# MCU.net
KiCad netlist of a schematic drawn in Altium Designer
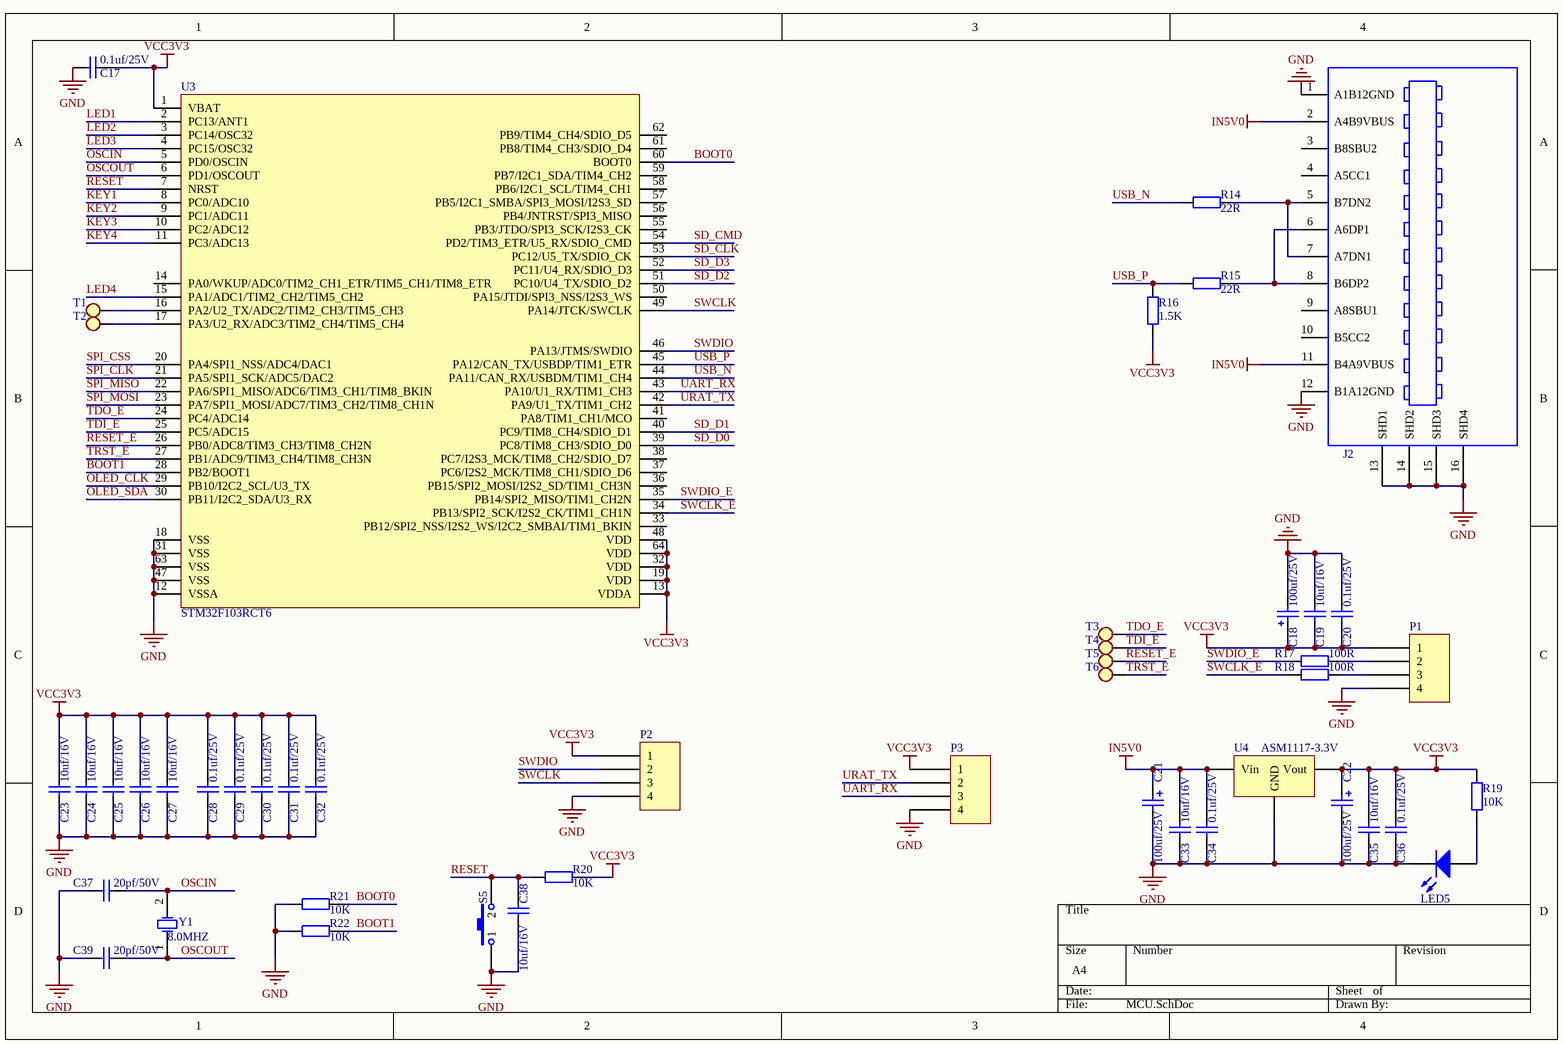
[diagram p0: MCU.SchDoc]

(export (version "E")
  (design (tool "Eeschema 10.0.6"))
  (components
    (comp (ref "C17")
      (value "0.1uf/25V")
      (footprint "R_C_L:C_0603")
      (description "多层片式陶瓷电容器")
      (libsource (lib "R_C_L") (part "C-0603-0.1uf/25V-10%"))
    )
    (comp (ref "C18")
      (value "100uf/25V")
      (footprint "R_C_L:C_6.3*5.4")
      (description "贴片电解电容")
      (libsource (lib "R_C_L") (part "C-6.3*5.8mm-100uf/25V-20%"))
    )
    (comp (ref "C19")
      (value "10uf/16V")
      (footprint "R_C_L:C_0603")
      (description "多层片式陶瓷电容器")
      (libsource (lib "R_C_L") (part "C-0603-10uf/16V-10%"))
    )
    (comp (ref "C20")
      (value "0.1uf/25V")
      (footprint "R_C_L:C_0603")
      (description "多层片式陶瓷电容器")
      (libsource (lib "R_C_L") (part "C-0603-0.1uf/25V-10%"))
    )
    (comp (ref "C21")
      (value "100uf/25V")
      (footprint "R_C_L:C_6.3*5.4")
      (description "贴片电解电容")
      (libsource (lib "R_C_L") (part "C-6.3*5.8mm-100uf/25V-20%"))
    )
    (comp (ref "C22")
      (value "100uf/25V")
      (footprint "R_C_L:C_6.3*5.4")
      (description "贴片电解电容")
      (libsource (lib "R_C_L") (part "C-6.3*5.8mm-100uf/25V-20%"))
    )
    (comp (ref "C23")
      (value "10uf/16V")
      (footprint "R_C_L:C_0603")
      (description "多层片式陶瓷电容器")
      (libsource (lib "R_C_L") (part "C-0603-10uf/16V-10%"))
    )
    (comp (ref "C24")
      (value "10uf/16V")
      (footprint "R_C_L:C_0603")
      (description "多层片式陶瓷电容器")
      (libsource (lib "R_C_L") (part "C-0603-10uf/16V-10%"))
    )
    (comp (ref "C25")
      (value "10uf/16V")
      (footprint "R_C_L:C_0603")
      (description "多层片式陶瓷电容器")
      (libsource (lib "R_C_L") (part "C-0603-10uf/16V-10%"))
    )
    (comp (ref "C26")
      (value "10uf/16V")
      (footprint "R_C_L:C_0603")
      (description "多层片式陶瓷电容器")
      (libsource (lib "R_C_L") (part "C-0603-10uf/16V-10%"))
    )
    (comp (ref "C27")
      (value "10uf/16V")
      (footprint "R_C_L:C_0603")
      (description "多层片式陶瓷电容器")
      (libsource (lib "R_C_L") (part "C-0603-10uf/16V-10%"))
    )
    (comp (ref "C28")
      (value "0.1uf/25V")
      (footprint "R_C_L:C_0603")
      (description "多层片式陶瓷电容器")
      (libsource (lib "R_C_L") (part "C-0603-0.1uf/25V-10%"))
    )
    (comp (ref "C29")
      (value "0.1uf/25V")
      (footprint "R_C_L:C_0603")
      (description "多层片式陶瓷电容器")
      (libsource (lib "R_C_L") (part "C-0603-0.1uf/25V-10%"))
    )
    (comp (ref "C30")
      (value "0.1uf/25V")
      (footprint "R_C_L:C_0603")
      (description "多层片式陶瓷电容器")
      (libsource (lib "R_C_L") (part "C-0603-0.1uf/25V-10%"))
    )
    (comp (ref "C31")
      (value "0.1uf/25V")
      (footprint "R_C_L:C_0603")
      (description "多层片式陶瓷电容器")
      (libsource (lib "R_C_L") (part "C-0603-0.1uf/25V-10%"))
    )
    (comp (ref "C32")
      (value "0.1uf/25V")
      (footprint "R_C_L:C_0603")
      (description "多层片式陶瓷电容器")
      (libsource (lib "R_C_L") (part "C-0603-0.1uf/25V-10%"))
    )
    (comp (ref "C33")
      (value "10uf/16V")
      (footprint "R_C_L:C_0603")
      (description "多层片式陶瓷电容器")
      (libsource (lib "R_C_L") (part "C-0603-10uf/16V-10%"))
    )
    (comp (ref "C34")
      (value "0.1uf/25V")
      (footprint "R_C_L:C_0603")
      (description "多层片式陶瓷电容器")
      (libsource (lib "R_C_L") (part "C-0603-0.1uf/25V-10%"))
    )
    (comp (ref "C35")
      (value "10uf/16V")
      (footprint "R_C_L:C_0603")
      (description "多层片式陶瓷电容器")
      (libsource (lib "R_C_L") (part "C-0603-10uf/16V-10%"))
    )
    (comp (ref "C36")
      (value "0.1uf/25V")
      (footprint "R_C_L:C_0603")
      (description "多层片式陶瓷电容器")
      (libsource (lib "R_C_L") (part "C-0603-0.1uf/25V-10%"))
    )
    (comp (ref "C37")
      (value "20pf/50V")
      (footprint "R_C_L:C_0603")
      (description "多层片式陶瓷电容器")
      (libsource (lib "R_C_L") (part "C-0603-20pf/50V-5%"))
    )
    (comp (ref "C38")
      (value "10uf/16V")
      (footprint "R_C_L:C_0603")
      (description "多层片式陶瓷电容器")
      (libsource (lib "R_C_L") (part "C-0603-10uf/16V-10%"))
    )
    (comp (ref "C39")
      (value "20pf/50V")
      (footprint "R_C_L:C_0603")
      (description "多层片式陶瓷电容器")
      (libsource (lib "R_C_L") (part "C-0603-20pf/50V-5%"))
    )
    (comp (ref "J2")
      (value "USB_TYPEC_YBT_2V0")
      (footprint "USB_TYPEC_YBD_USB31")
      (description "type-c母座16pin 快充闪充usb3.0沉板母座连接")
      (libsource (lib "HYG_Connector") (part "USB_TYPEC_YBT_2V0"))
    )
    (comp (ref "LED5")
      (value "19-21SYGC/S530-E2/TR8")
      (footprint "Transistor:LED_0603")
      (description "发光二极管0603黄绿色")
      (libsource (lib "Transistor") (part "LED1_19-21SYGC/S530-E2/TR8"))
    )
    (comp (ref "P1")
      (value "A2543WR-4P-2")
      (footprint "XH2.54-LI-4P")
      (libsource (lib "Connector") (part "Header 4*1   2.54mm直插  A2543WR-4P-2"))
    )
    (comp (ref "P2")
      (value "210S-1*4P L=11.6MM镀金")
      (footprint "Connector:CON2.54-4P-A-DIP")
      (libsource (lib "Connector") (part "Header 4*1   2.54mm直插  210S-1*4P L=11.6MM镀金"))
    )
    (comp (ref "P3")
      (value "210S-1*4P L=11.6MM镀金")
      (footprint "Connector:CON2.54-4P-A-DIP")
      (libsource (lib "Connector") (part "Header 4*1   2.54mm直插  210S-1*4P L=11.6MM镀金"))
    )
    (comp (ref "R14")
      (value "22R")
      (footprint "R_C_L:R_0603")
      (description "通用电阻")
      (libsource (lib "R_C_L") (part "R-0603-22R-1%"))
    )
    (comp (ref "R15")
      (value "22R")
      (footprint "R_C_L:R_0603")
      (description "通用电阻")
      (libsource (lib "R_C_L") (part "R-0603-22R-1%"))
    )
    (comp (ref "R16")
      (value "1.5K")
      (footprint "R_C_L:R_0603")
      (description "通用电阻")
      (libsource (lib "R_C_L") (part "R-0603-1.5K-1%"))
    )
    (comp (ref "R17")
      (value "100R")
      (footprint "R_C_L:R_0603")
      (description "通用电阻")
      (libsource (lib "R_C_L") (part "R-0603-100R-1%"))
    )
    (comp (ref "R18")
      (value "100R")
      (footprint "R_C_L:R_0603")
      (description "通用电阻")
      (libsource (lib "R_C_L") (part "R-0603-100R-1%"))
    )
    (comp (ref "R19")
      (value "10K")
      (footprint "R_C_L:R_0603")
      (description "通用电阻")
      (libsource (lib "R_C_L") (part "R-0603-10K-1%"))
    )
    (comp (ref "R20")
      (value "10K")
      (footprint "R_C_L:R_0603")
      (description "通用电阻")
      (libsource (lib "") (part "R-0603-10K-1%_1"))
    )
    (comp (ref "R21")
      (value "10K")
      (footprint "R_C_L:R_0603")
      (description "通用电阻")
      (libsource (lib "") (part "R-0603-10K-1%_1"))
    )
    (comp (ref "R22")
      (value "10K")
      (footprint "R_C_L:R_0603")
      (description "通用电阻")
      (libsource (lib "") (part "R-0603-10K-1%_1"))
    )
    (comp (ref "S5")
      (value "K2-1107ST-A4SW-06")
      (footprint "NSP:SW-2P-6*3-SMT")
      (description "轻触开关3.6*6.1*2.5")
      (libsource (lib "NSP") (part "KEY_K2-1107ST-A4SW-06"))
    )
    (comp (ref "T1")
      (value "TEST POINT_SMD")
      (footprint "NSP:TEST POINT-SMD")
      (description "测试点")
      (libsource (lib "NSP") (part "TEST POINT_SMD"))
    )
    (comp (ref "T2")
      (value "TEST POINT_SMD")
      (footprint "NSP:TEST POINT-SMD")
      (description "测试点")
      (libsource (lib "NSP") (part "TEST POINT_SMD"))
    )
    (comp (ref "T3")
      (value "TEST POINT_SMD")
      (footprint "NSP:TEST POINT-SMD")
      (description "测试点")
      (libsource (lib "NSP") (part "TEST POINT_SMD"))
    )
    (comp (ref "T4")
      (value "TEST POINT_SMD")
      (footprint "NSP:TEST POINT-SMD")
      (description "测试点")
      (libsource (lib "NSP") (part "TEST POINT_SMD"))
    )
    (comp (ref "T5")
      (value "TEST POINT_SMD")
      (footprint "NSP:TEST POINT-SMD")
      (description "测试点")
      (libsource (lib "NSP") (part "TEST POINT_SMD"))
    )
    (comp (ref "T6")
      (value "TEST POINT_SMD")
      (footprint "NSP:TEST POINT-SMD")
      (description "测试点")
      (libsource (lib "NSP") (part "TEST POINT_SMD"))
    )
    (comp (ref "U3")
      (value "STM32F103RCT6")
      (footprint "Digital:LQFP64")
      (description "Cortex-M3核心ARM控制器 72MHz主频 64pin引脚LQFP64")
      (libsource (lib "Digital") (part "STM32F103RCT6"))
    )
    (comp (ref "U4")
      (value "ASM1117-3.3V")
      (footprint "Power:SOT223")
      (description "三端稳压器")
      (libsource (lib "Power") (part "ASM1117-3.3V"))
    )
    (comp (ref "Y1")
      (value "8.0MHZ")
      (footprint "XTAL_5032")
      (description "晶体振荡器  5032-2P   8M")
      (libsource (lib "NSP") (part "XTAL_ABM3B-8.000MHZ-10-1-U-T"))
    )
  )
  (nets
    (net (code "1") (name "/BOOT0") (class "Default")
      (node (ref "R21") (pin "2") (pinfunction "2_2") (pintype "passive"))
      (node (ref "U3") (pin "60") (pinfunction "BOOT0_60") (pintype "passive"))
    )
    (net (code "2") (name "/BOOT1") (class "Default")
      (node (ref "R22") (pin "2") (pinfunction "2_2") (pintype "passive"))
      (node (ref "U3") (pin "28") (pinfunction "PB2/BOOT1_28") (pintype "passive"))
    )
    (net (code "3") (name "/KEY1") (class "Default")
      (node (ref "U3") (pin "8") (pinfunction "PC0/ADC10_8") (pintype "passive"))
    )
    (net (code "4") (name "/KEY2") (class "Default")
      (node (ref "U3") (pin "9") (pinfunction "PC1/ADC11_9") (pintype "passive"))
    )
    (net (code "5") (name "/KEY3") (class "Default")
      (node (ref "U3") (pin "10") (pinfunction "PC2/ADC12_10") (pintype "passive"))
    )
    (net (code "6") (name "/KEY4") (class "Default")
      (node (ref "U3") (pin "11") (pinfunction "PC3/ADC13_11") (pintype "passive"))
    )
    (net (code "7") (name "/LED1") (class "Default")
      (node (ref "U3") (pin "2") (pinfunction "PC13/ANT1_2") (pintype "passive"))
    )
    (net (code "8") (name "/LED2") (class "Default")
      (node (ref "U3") (pin "3") (pinfunction "PC14/OSC32_3") (pintype "passive"))
    )
    (net (code "9") (name "/LED3") (class "Default")
      (node (ref "U3") (pin "4") (pinfunction "PC15/OSC32_4") (pintype "passive"))
    )
    (net (code "10") (name "/LED4") (class "Default")
      (node (ref "U3") (pin "15") (pinfunction "PA1/ADC1/TIM2_CH2/TIM5_CH2_15") (pintype "passive"))
    )
    (net (code "11") (name "/OLED_CLK") (class "Default")
      (node (ref "U3") (pin "29") (pinfunction "PB10/I2C2_SCL/U3_TX_29") (pintype "passive"))
    )
    (net (code "12") (name "/OLED_SDA") (class "Default")
      (node (ref "U3") (pin "30") (pinfunction "PB11/I2C2_SDA/U3_RX_30") (pintype "passive"))
    )
    (net (code "13") (name "/OSCIN") (class "Default")
      (node (ref "C37") (pin "2") (pinfunction "2_2") (pintype "passive"))
      (node (ref "U3") (pin "5") (pinfunction "PD0/OSCIN_5") (pintype "passive"))
      (node (ref "Y1") (pin "2") (pinfunction "OSC2_2") (pintype "passive"))
    )
    (net (code "14") (name "/OSCOUT") (class "Default")
      (node (ref "C39") (pin "2") (pinfunction "2_2") (pintype "passive"))
      (node (ref "U3") (pin "6") (pinfunction "PD1/OSCOUT_6") (pintype "passive"))
      (node (ref "Y1") (pin "1") (pinfunction "OSC1_1") (pintype "passive"))
    )
    (net (code "15") (name "/RESET") (class "Default")
      (node (ref "C38") (pin "2") (pinfunction "2_2") (pintype "passive"))
      (node (ref "R20") (pin "1") (pinfunction "1_1") (pintype "passive"))
      (node (ref "S5") (pin "2") (pinfunction "2_2") (pintype "passive"))
      (node (ref "U3") (pin "7") (pinfunction "NRST_7") (pintype "passive"))
    )
    (net (code "16") (name "/RESET_E") (class "Default")
      (node (ref "T5") (pin "1") (pinfunction "1_1") (pintype "passive"))
      (node (ref "U3") (pin "26") (pinfunction "PB0/ADC8/TIM3_CH3/TIM8_CH2N_26") (pintype "passive"))
    )
    (net (code "17") (name "/SD_CLK") (class "Default")
      (node (ref "U3") (pin "53") (pinfunction "PC12/U5_TX/SDIO_CK_53") (pintype "passive"))
    )
    (net (code "18") (name "/SD_CMD") (class "Default")
      (node (ref "U3") (pin "54") (pinfunction "PD2/TIM3_ETR/U5_RX/SDIO_CMD_54") (pintype "passive"))
    )
    (net (code "19") (name "/SD_D0") (class "Default")
      (node (ref "U3") (pin "39") (pinfunction "PC8/TIM8_CH3/SDIO_D0_39") (pintype "passive"))
    )
    (net (code "20") (name "/SD_D1") (class "Default")
      (node (ref "U3") (pin "40") (pinfunction "PC9/TIM8_CH4/SDIO_D1_40") (pintype "passive"))
    )
    (net (code "21") (name "/SD_D2") (class "Default")
      (node (ref "U3") (pin "51") (pinfunction "PC10/U4_TX/SDIO_D2_51") (pintype "passive"))
    )
    (net (code "22") (name "/SD_D3") (class "Default")
      (node (ref "U3") (pin "52") (pinfunction "PC11/U4_RX/SDIO_D3_52") (pintype "passive"))
    )
    (net (code "23") (name "/SPI_CLK") (class "Default")
      (node (ref "U3") (pin "21") (pinfunction "PA5/SPI1_SCK/ADC5/DAC2_21") (pintype "passive"))
    )
    (net (code "24") (name "/SPI_CSS") (class "Default")
      (node (ref "U3") (pin "20") (pinfunction "PA4/SPI1_NSS/ADC4/DAC1_20") (pintype "passive"))
    )
    (net (code "25") (name "/SPI_MISO") (class "Default")
      (node (ref "U3") (pin "22") (pinfunction "PA6/SPI1_MISO/ADC6/TIM3_CH1/TIM8_BKIN_22") (pintype "passive"))
    )
    (net (code "26") (name "/SPI_MOSI") (class "Default")
      (node (ref "U3") (pin "23") (pinfunction "PA7/SPI1_MOSI/ADC7/TIM3_CH2/TIM8_CH1N_23") (pintype "passive"))
    )
    (net (code "27") (name "/SWCLK") (class "Default")
      (node (ref "P2") (pin "3") (pinfunction "3_3") (pintype "passive"))
      (node (ref "U3") (pin "49") (pinfunction "PA14/JTCK/SWCLK_49") (pintype "passive"))
    )
    (net (code "28") (name "/SWCLK_E") (class "Default")
      (node (ref "R18") (pin "1") (pinfunction "1_1") (pintype "passive"))
      (node (ref "U3") (pin "34") (pinfunction "PB13/SPI2_SCK/I2S2_CK/TIM1_CH1N_34") (pintype "passive"))
    )
    (net (code "29") (name "/SWDIO") (class "Default")
      (node (ref "P2") (pin "2") (pinfunction "2_2") (pintype "passive"))
      (node (ref "U3") (pin "46") (pinfunction "PA13/JTMS/SWDIO_46") (pintype "passive"))
    )
    (net (code "30") (name "/SWDIO_E") (class "Default")
      (node (ref "R17") (pin "1") (pinfunction "1_1") (pintype "passive"))
      (node (ref "U3") (pin "35") (pinfunction "PB14/SPI2_MISO/TIM1_CH2N_35") (pintype "passive"))
    )
    (net (code "31") (name "/TDI_E") (class "Default")
      (node (ref "T4") (pin "1") (pinfunction "1_1") (pintype "passive"))
      (node (ref "U3") (pin "25") (pinfunction "PC5/ADC15_25") (pintype "passive"))
    )
    (net (code "32") (name "/TDO_E") (class "Default")
      (node (ref "T3") (pin "1") (pinfunction "1_1") (pintype "passive"))
      (node (ref "U3") (pin "24") (pinfunction "PC4/ADC14_24") (pintype "passive"))
    )
    (net (code "33") (name "/TRST_E") (class "Default")
      (node (ref "T6") (pin "1") (pinfunction "1_1") (pintype "passive"))
      (node (ref "U3") (pin "27") (pinfunction "PB1/ADC9/TIM3_CH4/TIM8_CH3N_27") (pintype "passive"))
    )
    (net (code "34") (name "/UART_RX") (class "Default")
      (node (ref "P3") (pin "3") (pinfunction "3_3") (pintype "passive"))
      (node (ref "U3") (pin "43") (pinfunction "PA10/U1_RX/TIM1_CH3_43") (pintype "passive"))
    )
    (net (code "35") (name "/URAT_TX") (class "Default")
      (node (ref "P3") (pin "2") (pinfunction "2_2") (pintype "passive"))
      (node (ref "U3") (pin "42") (pinfunction "PA9/U1_TX/TIM1_CH2_42") (pintype "passive"))
    )
    (net (code "36") (name "/USB_N") (class "Default")
      (node (ref "R14") (pin "1") (pinfunction "1_1") (pintype "passive"))
      (node (ref "U3") (pin "44") (pinfunction "PA11/CAN_RX/USBDM/TIM1_CH4_44") (pintype "passive"))
    )
    (net (code "37") (name "/USB_P") (class "Default")
      (node (ref "R15") (pin "1") (pinfunction "1_1") (pintype "passive"))
      (node (ref "R16") (pin "2") (pinfunction "2_2") (pintype "passive"))
      (node (ref "U3") (pin "45") (pinfunction "PA12/CAN_TX/USBDP/TIM1_ETR_45") (pintype "passive"))
    )
    (net (code "38") (name "GND") (class "Default")
      (node (ref "C17") (pin "1") (pinfunction "1_1") (pintype "passive"))
      (node (ref "C18") (pin "2") (pinfunction "2_2") (pintype "passive"))
      (node (ref "C19") (pin "2") (pinfunction "2_2") (pintype "passive"))
      (node (ref "C20") (pin "2") (pinfunction "2_2") (pintype "passive"))
      (node (ref "C21") (pin "2") (pinfunction "2_2") (pintype "passive"))
      (node (ref "C22") (pin "2") (pinfunction "2_2") (pintype "passive"))
      (node (ref "C23") (pin "1") (pinfunction "1_1") (pintype "passive"))
      (node (ref "C24") (pin "1") (pinfunction "1_1") (pintype "passive"))
      (node (ref "C25") (pin "1") (pinfunction "1_1") (pintype "passive"))
      (node (ref "C26") (pin "1") (pinfunction "1_1") (pintype "passive"))
      (node (ref "C27") (pin "1") (pinfunction "1_1") (pintype "passive"))
      (node (ref "C28") (pin "1") (pinfunction "1_1") (pintype "passive"))
      (node (ref "C29") (pin "1") (pinfunction "1_1") (pintype "passive"))
      (node (ref "C30") (pin "1") (pinfunction "1_1") (pintype "passive"))
      (node (ref "C31") (pin "1") (pinfunction "1_1") (pintype "passive"))
      (node (ref "C32") (pin "1") (pinfunction "1_1") (pintype "passive"))
      (node (ref "C33") (pin "1") (pinfunction "1_1") (pintype "passive"))
      (node (ref "C34") (pin "1") (pinfunction "1_1") (pintype "passive"))
      (node (ref "C35") (pin "1") (pinfunction "1_1") (pintype "passive"))
      (node (ref "C36") (pin "1") (pinfunction "1_1") (pintype "passive"))
      (node (ref "C37") (pin "1") (pinfunction "1_1") (pintype "passive"))
      (node (ref "C38") (pin "1") (pinfunction "1_1") (pintype "passive"))
      (node (ref "C39") (pin "1") (pinfunction "1_1") (pintype "passive"))
      (node (ref "J2") (pin "1") (pinfunction "A1B12GND_1") (pintype "passive"))
      (node (ref "J2") (pin "12") (pinfunction "B1A12GND_12") (pintype "passive"))
      (node (ref "J2") (pin "13") (pinfunction "SHD1_13") (pintype "passive"))
      (node (ref "J2") (pin "14") (pinfunction "SHD2_14") (pintype "passive"))
      (node (ref "J2") (pin "15") (pinfunction "SHD3_15") (pintype "passive"))
      (node (ref "J2") (pin "16") (pinfunction "SHD4_16") (pintype "passive"))
      (node (ref "LED5") (pin "2") (pinfunction "Cathode_2") (pintype "passive"))
      (node (ref "P1") (pin "4") (pinfunction "4_4") (pintype "passive"))
      (node (ref "P2") (pin "4") (pinfunction "4_4") (pintype "passive"))
      (node (ref "P3") (pin "4") (pinfunction "4_4") (pintype "passive"))
      (node (ref "R21") (pin "1") (pinfunction "1_1") (pintype "passive"))
      (node (ref "R22") (pin "1") (pinfunction "1_1") (pintype "passive"))
      (node (ref "S5") (pin "1") (pinfunction "1_1") (pintype "passive"))
      (node (ref "U3") (pin "12") (pinfunction "VSSA_12") (pintype "passive"))
      (node (ref "U3") (pin "18") (pinfunction "VSS_18") (pintype "passive"))
      (node (ref "U3") (pin "31") (pinfunction "VSS_31") (pintype "passive"))
      (node (ref "U3") (pin "47") (pinfunction "VSS_47") (pintype "passive"))
      (node (ref "U3") (pin "63") (pinfunction "VSS_63") (pintype "passive"))
      (node (ref "U4") (pin "1") (pinfunction "GND_1") (pintype "passive"))
    )
    (net (code "39") (name "IN5V0") (class "Default")
      (node (ref "C21") (pin "1") (pinfunction "1_1") (pintype "passive"))
      (node (ref "C33") (pin "2") (pinfunction "2_2") (pintype "passive"))
      (node (ref "C34") (pin "2") (pinfunction "2_2") (pintype "passive"))
      (node (ref "J2") (pin "11") (pinfunction "B4A9VBUS_11") (pintype "passive"))
      (node (ref "J2") (pin "2") (pinfunction "A4B9VBUS_2") (pintype "passive"))
      (node (ref "U4") (pin "3") (pinfunction "Vin_3") (pintype "passive"))
    )
    (net (code "40") (name "Net-(J2-A6DP1)") (class "Default")
      (node (ref "J2") (pin "6") (pinfunction "A6DP1_6") (pintype "passive"))
      (node (ref "J2") (pin "8") (pinfunction "B6DP2_8") (pintype "passive"))
      (node (ref "R15") (pin "2") (pinfunction "2_2") (pintype "passive"))
    )
    (net (code "41") (name "Net-(J2-A7DN1)") (class "Default")
      (node (ref "J2") (pin "5") (pinfunction "B7DN2_5") (pintype "passive"))
      (node (ref "J2") (pin "7") (pinfunction "A7DN1_7") (pintype "passive"))
      (node (ref "R14") (pin "2") (pinfunction "2_2") (pintype "passive"))
    )
    (net (code "42") (name "Net-(LED5-Anode)") (class "Default")
      (node (ref "LED5") (pin "1") (pinfunction "Anode_1") (pintype "passive"))
      (node (ref "R19") (pin "1") (pinfunction "1_1") (pintype "passive"))
    )
    (net (code "43") (name "Net-(P1-Pad2)") (class "Default")
      (node (ref "P1") (pin "2") (pinfunction "2_2") (pintype "passive"))
      (node (ref "R17") (pin "2") (pinfunction "2_2") (pintype "passive"))
    )
    (net (code "44") (name "Net-(P1-Pad3)") (class "Default")
      (node (ref "P1") (pin "3") (pinfunction "3_3") (pintype "passive"))
      (node (ref "R18") (pin "2") (pinfunction "2_2") (pintype "passive"))
    )
    (net (code "45") (name "Net-(U3-PA2{slash}U2_TX{slash}ADC2{slash}TIM2_CH3{slash}TIM5_CH3)") (class "Default")
      (node (ref "T1") (pin "1") (pinfunction "1_1") (pintype "passive"))
      (node (ref "U3") (pin "16") (pinfunction "PA2/U2_TX/ADC2/TIM2_CH3/TIM5_CH3_16") (pintype "passive"))
    )
    (net (code "46") (name "Net-(U3-PA3{slash}U2_RX{slash}ADC3{slash}TIM2_CH4{slash}TIM5_CH4)") (class "Default")
      (node (ref "T2") (pin "1") (pinfunction "1_1") (pintype "passive"))
      (node (ref "U3") (pin "17") (pinfunction "PA3/U2_RX/ADC3/TIM2_CH4/TIM5_CH4_17") (pintype "passive"))
    )
    (net (code "47") (name "VCC3V3") (class "Default")
      (node (ref "C17") (pin "2") (pinfunction "2_2") (pintype "passive"))
      (node (ref "C18") (pin "1") (pinfunction "1_1") (pintype "passive"))
      (node (ref "C19") (pin "1") (pinfunction "1_1") (pintype "passive"))
      (node (ref "C20") (pin "1") (pinfunction "1_1") (pintype "passive"))
      (node (ref "C22") (pin "1") (pinfunction "1_1") (pintype "passive"))
      (node (ref "C23") (pin "2") (pinfunction "2_2") (pintype "passive"))
      (node (ref "C24") (pin "2") (pinfunction "2_2") (pintype "passive"))
      (node (ref "C25") (pin "2") (pinfunction "2_2") (pintype "passive"))
      (node (ref "C26") (pin "2") (pinfunction "2_2") (pintype "passive"))
      (node (ref "C27") (pin "2") (pinfunction "2_2") (pintype "passive"))
      (node (ref "C28") (pin "2") (pinfunction "2_2") (pintype "passive"))
      (node (ref "C29") (pin "2") (pinfunction "2_2") (pintype "passive"))
      (node (ref "C30") (pin "2") (pinfunction "2_2") (pintype "passive"))
      (node (ref "C31") (pin "2") (pinfunction "2_2") (pintype "passive"))
      (node (ref "C32") (pin "2") (pinfunction "2_2") (pintype "passive"))
      (node (ref "C35") (pin "2") (pinfunction "2_2") (pintype "passive"))
      (node (ref "C36") (pin "2") (pinfunction "2_2") (pintype "passive"))
      (node (ref "P1") (pin "1") (pinfunction "1_1") (pintype "passive"))
      (node (ref "P2") (pin "1") (pinfunction "1_1") (pintype "passive"))
      (node (ref "P3") (pin "1") (pinfunction "1_1") (pintype "passive"))
      (node (ref "R16") (pin "1") (pinfunction "1_1") (pintype "passive"))
      (node (ref "R19") (pin "2") (pinfunction "2_2") (pintype "passive"))
      (node (ref "R20") (pin "2") (pinfunction "2_2") (pintype "passive"))
      (node (ref "U3") (pin "1") (pinfunction "VBAT_1") (pintype "passive"))
      (node (ref "U3") (pin "13") (pinfunction "VDDA_13") (pintype "passive"))
      (node (ref "U3") (pin "19") (pinfunction "VDD_19") (pintype "passive"))
      (node (ref "U3") (pin "32") (pinfunction "VDD_32") (pintype "passive"))
      (node (ref "U3") (pin "48") (pinfunction "VDD_48") (pintype "passive"))
      (node (ref "U3") (pin "64") (pinfunction "VDD_64") (pintype "passive"))
      (node (ref "U4") (pin "2") (pinfunction "Vout_2") (pintype "passive"))
    )
    (net (code "48") (name "unconnected-(J2-A5CC1-Pad4)") (class "Default")
      (node (ref "J2") (pin "4") (pinfunction "A5CC1_4") (pintype "passive"))
    )
    (net (code "49") (name "unconnected-(J2-A8SBU1-Pad9)") (class "Default")
      (node (ref "J2") (pin "9") (pinfunction "A8SBU1_9") (pintype "passive"))
    )
    (net (code "50") (name "unconnected-(J2-B5CC2-Pad10)") (class "Default")
      (node (ref "J2") (pin "10") (pinfunction "B5CC2_10") (pintype "passive"))
    )
    (net (code "51") (name "unconnected-(J2-B8SBU2-Pad3)") (class "Default")
      (node (ref "J2") (pin "3") (pinfunction "B8SBU2_3") (pintype "passive"))
    )
    (net (code "52") (name "unconnected-(U3-PA0{slash}WKUP{slash}ADC0{slash}TIM2_CH1_ETR{slash}TIM5_CH1{slash}TIM8_ETR-Pad14)") (class "Default")
      (node (ref "U3") (pin "14") (pinfunction "PA0/WKUP/ADC0/TIM2_CH1_ETR/TIM5_CH1/TIM8_ETR_14") (pintype "passive"))
    )
    (net (code "53") (name "unconnected-(U3-PA8{slash}TIM1_CH1{slash}MCO-Pad41)") (class "Default")
      (node (ref "U3") (pin "41") (pinfunction "PA8/TIM1_CH1/MCO_41") (pintype "passive"))
    )
    (net (code "54") (name "unconnected-(U3-PA15{slash}JTDI{slash}SPI3_NSS{slash}I2S3_WS-Pad50)") (class "Default")
      (node (ref "U3") (pin "50") (pinfunction "PA15/JTDI/SPI3_NSS/I2S3_WS_50") (pintype "passive"))
    )
    (net (code "55") (name "unconnected-(U3-PB3{slash}JTDO{slash}SPI3_SCK{slash}I2S3_CK-Pad55)") (class "Default")
      (node (ref "U3") (pin "55") (pinfunction "PB3/JTDO/SPI3_SCK/I2S3_CK_55") (pintype "passive"))
    )
    (net (code "56") (name "unconnected-(U3-PB4{slash}JNTRST{slash}SPI3_MISO-Pad56)") (class "Default")
      (node (ref "U3") (pin "56") (pinfunction "PB4/JNTRST/SPI3_MISO_56") (pintype "passive"))
    )
    (net (code "57") (name "unconnected-(U3-PB5{slash}I2C1_SMBA{slash}SPI3_MOSI{slash}I2S3_SD-Pad57)") (class "Default")
      (node (ref "U3") (pin "57") (pinfunction "PB5/I2C1_SMBA/SPI3_MOSI/I2S3_SD_57") (pintype "passive"))
    )
    (net (code "58") (name "unconnected-(U3-PB6{slash}I2C1_SCL{slash}TIM4_CH1-Pad58)") (class "Default")
      (node (ref "U3") (pin "58") (pinfunction "PB6/I2C1_SCL/TIM4_CH1_58") (pintype "passive"))
    )
    (net (code "59") (name "unconnected-(U3-PB7{slash}I2C1_SDA{slash}TIM4_CH2-Pad59)") (class "Default")
      (node (ref "U3") (pin "59") (pinfunction "PB7/I2C1_SDA/TIM4_CH2_59") (pintype "passive"))
    )
    (net (code "60") (name "unconnected-(U3-PB8{slash}TIM4_CH3{slash}SDIO_D4-Pad61)") (class "Default")
      (node (ref "U3") (pin "61") (pinfunction "PB8/TIM4_CH3/SDIO_D4_61") (pintype "passive"))
    )
    (net (code "61") (name "unconnected-(U3-PB9{slash}TIM4_CH4{slash}SDIO_D5-Pad62)") (class "Default")
      (node (ref "U3") (pin "62") (pinfunction "PB9/TIM4_CH4/SDIO_D5_62") (pintype "passive"))
    )
    (net (code "62") (name "unconnected-(U3-PB12{slash}SPI2_NSS{slash}I2S2_WS{slash}I2C2_SMBAI{slash}TIM1_BKIN-Pad33)") (class "Default")
      (node (ref "U3") (pin "33") (pinfunction "PB12/SPI2_NSS/I2S2_WS/I2C2_SMBAI/TIM1_BKIN_33") (pintype "passive"))
    )
    (net (code "63") (name "unconnected-(U3-PB15{slash}SPI2_MOSI{slash}I2S2_SD{slash}TIM1_CH3N-Pad36)") (class "Default")
      (node (ref "U3") (pin "36") (pinfunction "PB15/SPI2_MOSI/I2S2_SD/TIM1_CH3N_36") (pintype "passive"))
    )
    (net (code "64") (name "unconnected-(U3-PC6{slash}I2S2_MCK{slash}TIM8_CH1{slash}SDIO_D6-Pad37)") (class "Default")
      (node (ref "U3") (pin "37") (pinfunction "PC6/I2S2_MCK/TIM8_CH1/SDIO_D6_37") (pintype "passive"))
    )
    (net (code "65") (name "unconnected-(U3-PC7{slash}I2S3_MCK{slash}TIM8_CH2{slash}SDIO_D7-Pad38)") (class "Default")
      (node (ref "U3") (pin "38") (pinfunction "PC7/I2S3_MCK/TIM8_CH2/SDIO_D7_38") (pintype "passive"))
    )
  )
)
